# Remot.net
KiCad netlist of a schematic drawn in Altium Designer
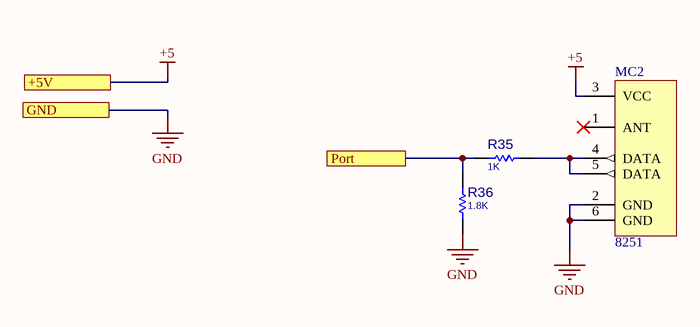
[diagram p0: Remot.SchDoc]

(export (version "E")
  (design (tool "Eeschema 10.0.6"))
  (components
    (comp (ref "MC2")
      (value "RXB22")
      (footprint "RF_ETRXB")
      (description "JMR RXB22 433MHz ASK superheterodyne wireless receiving module")
      (fields (field (name "INFLOW") "8251") (field (name "VALIDATION") "Valid"))
      (libsource (lib "aKaReZa") (part "ModSen_Com_RXB22_433"))
    )
    (comp (ref "R35")
      (value "1K")
      (footprint "R0805")
      (description "RESISTOR, SMD")
      (libsource (lib "Chila_PCB") (part "RES_SMD_0805"))
    )
    (comp (ref "R36")
      (value "1.8K")
      (footprint "R0805")
      (description "RESISTOR, SMD")
      (libsource (lib "Chila_PCB") (part "RES_SMD_0805"))
    )
  )
  (nets
    (net (code "1") (name "+5") (class "Default")
      (node (ref "MC2") (pin "3") (pinfunction "VCC_3") (pintype "power_in"))
    )
    (net (code "2") (name "/Port") (class "Default")
      (node (ref "R35") (pin "2") (pinfunction "2_2") (pintype "passive"))
      (node (ref "R36") (pin "2") (pinfunction "2_2") (pintype "passive"))
    )
    (net (code "3") (name "GND") (class "Default")
      (node (ref "MC2") (pin "2") (pinfunction "GND_2") (pintype "power_in"))
      (node (ref "MC2") (pin "6") (pinfunction "GND_6") (pintype "power_in"))
      (node (ref "R36") (pin "1") (pinfunction "1_1") (pintype "passive"))
    )
    (net (code "4") (name "Net-(MC2-DATA-Pad4)") (class "Default")
      (node (ref "MC2") (pin "4") (pinfunction "DATA_4") (pintype "output"))
      (node (ref "MC2") (pin "5") (pinfunction "DATA_5") (pintype "output"))
      (node (ref "R35") (pin "1") (pinfunction "1_1") (pintype "passive"))
    )
    (net (code "5") (name "unconnected-(MC2-ANT-Pad1)") (class "Default")
      (node (ref "MC2") (pin "1") (pinfunction "ANT_1") (pintype "passive+no_connect"))
    )
  )
)
